# ATtiny85Minimal.net
KiCad netlist of a schematic drawn in EAGLE
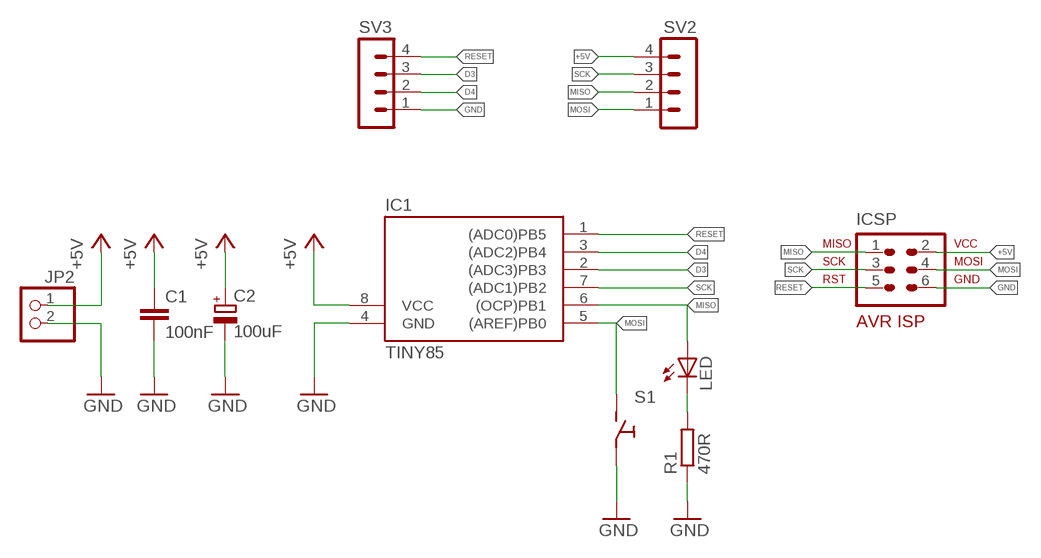
[diagram p0: schematic, sheet 1]

(export (version "E")
  (design (tool "Eeschema 10.0.6"))
  (components
    (comp (ref "C1")
      (value "100nF")
      (footprint "eagle-import:C025-030X050")
      (libsource (lib "eagle-import") (part "C-EU025-030X050"))
    )
    (comp (ref "C2")
      (value "100uF")
      (footprint "eagle-import:E2-5")
      (libsource (lib "eagle-import") (part "CPOL-EUE2-5"))
    )
    (comp (ref "IC1")
      (value "TINY85")
      (footprint "eagle-import:DIL08")
      (libsource (lib "eagle-import") (part "TINY25/45/85-20PU"))
    )
    (comp (ref "ICSP")
      (value "AVR-ISP-6VERT")
      (footprint "eagle-import:AVR-ISP-6")
      (libsource (lib "eagle-import") (part "AVR-ISP-6VERT"))
    )
    (comp (ref "JP2")
      (value "PINHD-1X2")
      (footprint "eagle-import:1X02")
      (libsource (lib "eagle-import") (part "PINHD-1X2"))
    )
    (comp (ref "LED")
      (value "LED3MM")
      (footprint "eagle-import:LED3MM")
      (libsource (lib "eagle-import") (part "LED3MM"))
    )
    (comp (ref "R1")
      (value "470R")
      (footprint "eagle-import:0207_7")
      (libsource (lib "eagle-import") (part "R-EU_0207/7"))
    )
    (comp (ref "S1")
      (value "TASTER")
      (footprint "eagle-import:MICROSCHALTER")
      (libsource (lib "eagle-import") (part "TASTER"))
    )
    (comp (ref "SV2")
      (value "MA04-1")
      (footprint "eagle-import:MA04-1")
      (libsource (lib "eagle-import") (part "MA04-1"))
    )
    (comp (ref "SV3")
      (value "MA04-1")
      (footprint "eagle-import:MA04-1")
      (libsource (lib "eagle-import") (part "MA04-1"))
    )
  )
  (nets
    (net (code "1") (name "+5V") (class "Default")
      (node (ref "C1") (pin "1") (pinfunction "1_1") (pintype "passive"))
      (node (ref "C2") (pin "+") (pinfunction "+_+") (pintype "passive"))
      (node (ref "IC1") (pin "8") (pinfunction "VCC_8") (pintype "power_in"))
      (node (ref "ICSP") (pin "2") (pinfunction "2_2") (pintype "passive"))
      (node (ref "JP2") (pin "1") (pinfunction "1_1") (pintype "passive"))
      (node (ref "SV2") (pin "4") (pinfunction "4_4") (pintype "passive"))
    )
    (net (code "2") (name "D3") (class "Default")
      (node (ref "IC1") (pin "2") (pinfunction "(ADC3)PB3_2") (pintype "bidirectional"))
      (node (ref "SV3") (pin "3") (pinfunction "3_3") (pintype "passive"))
    )
    (net (code "3") (name "D4") (class "Default")
      (node (ref "IC1") (pin "3") (pinfunction "(ADC2)PB4_3") (pintype "bidirectional"))
      (node (ref "SV3") (pin "2") (pinfunction "2_2") (pintype "passive"))
    )
    (net (code "4") (name "GND") (class "Default")
      (node (ref "C1") (pin "2") (pinfunction "2_2") (pintype "passive"))
      (node (ref "C2") (pin "-") (pinfunction "-_-") (pintype "passive"))
      (node (ref "IC1") (pin "4") (pinfunction "GND_4") (pintype "power_in"))
      (node (ref "ICSP") (pin "6") (pinfunction "6_6") (pintype "passive"))
      (node (ref "JP2") (pin "2") (pinfunction "2_2") (pintype "passive"))
      (node (ref "R1") (pin "1") (pinfunction "1_1") (pintype "passive"))
      (node (ref "S1") (pin "P$2") (pinfunction "P$3_P$2") (pintype "bidirectional"))
      (node (ref "SV3") (pin "1") (pinfunction "1_1") (pintype "passive"))
    )
    (net (code "5") (name "MISO") (class "Default")
      (node (ref "IC1") (pin "6") (pinfunction "(OCP)PB1_6") (pintype "bidirectional"))
      (node (ref "ICSP") (pin "1") (pinfunction "1_1") (pintype "passive"))
      (node (ref "LED") (pin "A") (pinfunction "A_A") (pintype "passive"))
      (node (ref "SV2") (pin "2") (pinfunction "2_2") (pintype "passive"))
    )
    (net (code "6") (name "MOSI") (class "Default")
      (node (ref "IC1") (pin "5") (pinfunction "(AREF)PB0_5") (pintype "bidirectional"))
      (node (ref "ICSP") (pin "4") (pinfunction "4_4") (pintype "passive"))
      (node (ref "S1") (pin "P$1") (pinfunction "P$1_P$1") (pintype "bidirectional"))
      (node (ref "SV2") (pin "1") (pinfunction "1_1") (pintype "passive"))
    )
    (net (code "7") (name "Net-(LED-C)") (class "Default")
      (node (ref "LED") (pin "K") (pinfunction "C_K") (pintype "passive"))
      (node (ref "R1") (pin "2") (pinfunction "2_2") (pintype "passive"))
    )
    (net (code "8") (name "RESET") (class "Default")
      (node (ref "IC1") (pin "1") (pinfunction "(ADC0)PB5_1") (pintype "bidirectional"))
      (node (ref "ICSP") (pin "5") (pinfunction "5_5") (pintype "passive"))
      (node (ref "SV3") (pin "4") (pinfunction "4_4") (pintype "passive"))
    )
    (net (code "9") (name "SCK") (class "Default")
      (node (ref "IC1") (pin "7") (pinfunction "(ADC1)PB2_7") (pintype "bidirectional"))
      (node (ref "ICSP") (pin "3") (pinfunction "3_3") (pintype "passive"))
      (node (ref "SV2") (pin "3") (pinfunction "3_3") (pintype "passive"))
    )
  )
)
